# Power.net
KiCad netlist of a schematic drawn in Altium Designer
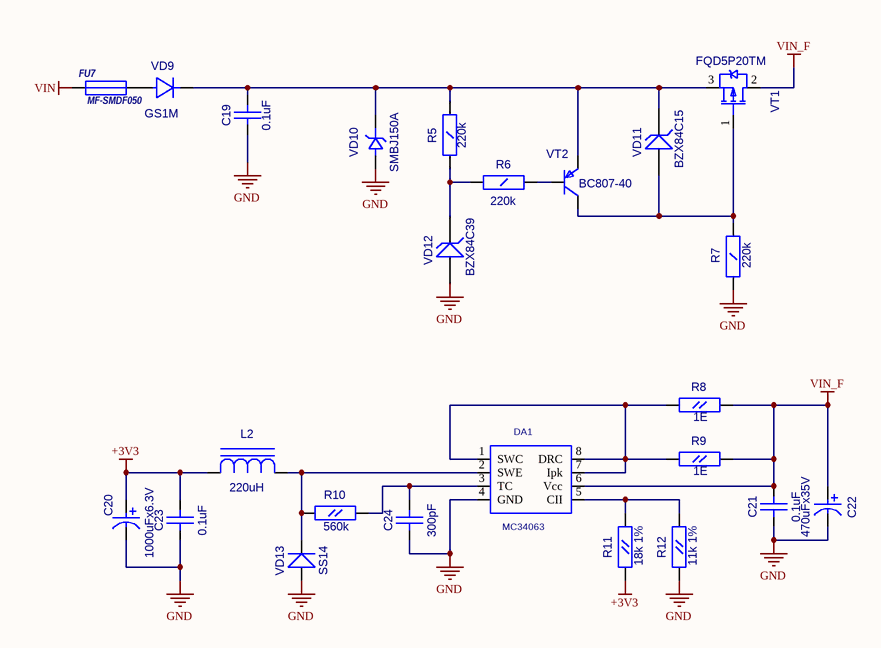
[diagram p0: Power.SchDoc]

(export (version "E")
  (design (tool "Eeschema 10.0.6"))
  (components
    (comp (ref "C19")
      (value "0.1uF")
      (footprint "CC1206")
      (description "CC1206")
      (libsource (lib "gprs_modem_2") (part "CC1206"))
    )
    (comp (ref "C20")
      (value "1000uFx6.3V")
      (footprint "CC8X3.5")
      (description "CAP0.35")
      (libsource (lib "gprs_modem_2") (part "CAP0.35"))
    )
    (comp (ref "C21")
      (value "0.1uF")
      (footprint "CC0603")
      (description "CC0603")
      (libsource (lib "gprs_modem_2") (part "CC0603"))
    )
    (comp (ref "C22")
      (value "470uFx35V")
      (footprint "CC16X10_CAP0.5(1)(Primary)")
      (description "CAP0.5(1)")
      (libsource (lib "gprs_modem_2") (part "CAP0.5(1)"))
    )
    (comp (ref "C23")
      (value "0.1uF")
      (footprint "CC0603")
      (description "CC0603")
      (libsource (lib "gprs_modem_2") (part "CC0603"))
    )
    (comp (ref "C24")
      (value "300pF")
      (footprint "CC0603")
      (description "CC0603")
      (libsource (lib "gprs_modem_2") (part "CC0603"))
    )
    (comp (ref "DA1") (value "MC34063") (footprint "SO-8") (libsource (lib "Schetchik") (part "MC34063")))
    (comp (ref "FU7")
      (value "MF-SMDF050")
      (footprint "MF-SMDF")
      (description "MF-SMDF")
      (libsource (lib "gprs_modem_2") (part "MF-SMDF"))
    )
    (comp (ref "L2")
      (value "220uH")
      (footprint "SDR0805")
      (description "SDR0805")
      (libsource (lib "gprs_modem_2") (part "SDR0805"))
    )
    (comp (ref "R5")
      (value "220k")
      (footprint "RC1206")
      (description "RC1206")
      (libsource (lib "gprs_modem_2") (part "RC1206"))
    )
    (comp (ref "R6")
      (value "220k")
      (footprint "RC1206")
      (description "RC1206")
      (libsource (lib "gprs_modem_2") (part "RC1206"))
    )
    (comp (ref "R7")
      (value "220k")
      (footprint "RC1206")
      (description "RC1206")
      (libsource (lib "gprs_modem_2") (part "RC1206"))
    )
    (comp (ref "R8")
      (value "1E")
      (footprint "RC0805")
      (description "RC0805")
      (libsource (lib "gprs_modem_2") (part "RC0805"))
    )
    (comp (ref "R9")
      (value "1E")
      (footprint "RC0805")
      (description "RC0805")
      (libsource (lib "gprs_modem_2") (part "RC0805"))
    )
    (comp (ref "R10")
      (value "560k")
      (footprint "RC0603")
      (description "RC0603")
      (libsource (lib "gprs_modem_2") (part "RC0603"))
    )
    (comp (ref "R11")
      (value "18k 1%")
      (footprint "RC0603")
      (description "RC0603")
      (libsource (lib "gprs_modem_2") (part "RC0603"))
    )
    (comp (ref "R12")
      (value "11k 1%")
      (footprint "RC0603")
      (description "RC0603")
      (libsource (lib "gprs_modem_2") (part "RC0603"))
    )
    (comp (ref "VD9") (value "GS1M") (footprint "SMA") (libsource (lib "gprs_modem") (part "GS1M")))
    (comp (ref "VD10")
      (value "SMBJ150A")
      (footprint "SMB")
      (description "SMBJ")
      (libsource (lib "gprs_modem_2") (part "SMBJ"))
    )
    (comp (ref "VD11")
      (value "BZX84C15")
      (footprint "SOT-23(123)")
      (description "Zener Voltage Regulator Diode")
      (libsource (lib "gprs_modem_2") (part "BZX84"))
    )
    (comp (ref "VD12")
      (value "BZX84C39")
      (footprint "SOT-23(123)")
      (description "Zener Voltage Regulator Diode")
      (libsource (lib "gprs_modem_2") (part "BZX84"))
    )
    (comp (ref "VD13")
      (value "SS14")
      (footprint "SMA")
      (description "Schottky Rectifier")
      (libsource (lib "gprs_modem_2") (part "SS14"))
    )
    (comp (ref "VT1")
      (value "FQD5P20TM")
      (footprint "D-PAK(TO-252AA)")
      (description "HEXFET Power MOSFET")
      (libsource (lib "gprs_modem_2") (part "IRFR9220"))
    )
    (comp (ref "VT2")
      (value "BC807-40")
      (footprint "SOT-23(123)")
      (description "BC857B")
      (libsource (lib "gprs_modem") (part "BC857B"))
    )
  )
  (nets
    (net (code "1") (name "+3V3") (class "Default")
      (node (ref "C20") (pin "1") (pintype "passive"))
      (node (ref "C23") (pin "2") (pinfunction "B_2") (pintype "passive"))
      (node (ref "L2") (pin "1") (pinfunction "C_1") (pintype "passive"))
      (node (ref "R11") (pin "1") (pinfunction "A_1") (pintype "passive"))
    )
    (net (code "2") (name "GND") (class "Default")
      (node (ref "C19") (pin "1") (pinfunction "A_1") (pintype "passive"))
      (node (ref "C20") (pin "2") (pintype "passive"))
      (node (ref "C21") (pin "1") (pinfunction "A_1") (pintype "passive"))
      (node (ref "C22") (pin "1") (pintype "passive"))
      (node (ref "C23") (pin "1") (pinfunction "A_1") (pintype "passive"))
      (node (ref "C24") (pin "1") (pinfunction "A_1") (pintype "passive"))
      (node (ref "DA1") (pin "4") (pinfunction "GND_4") (pintype "passive"))
      (node (ref "R12") (pin "1") (pinfunction "A_1") (pintype "passive"))
      (node (ref "R7") (pin "2") (pinfunction "B_2") (pintype "passive"))
      (node (ref "VD10") (pin "1") (pinfunction "A_1") (pintype "passive"))
      (node (ref "VD12") (pin "1") (pinfunction "A_1") (pintype "passive"))
      (node (ref "VD13") (pin "1") (pinfunction "A_1") (pintype "passive"))
    )
    (net (code "3") (name "Net-(C19-B)") (class "Default")
      (node (ref "C19") (pin "2") (pinfunction "B_2") (pintype "passive"))
      (node (ref "R5") (pin "2") (pinfunction "B_2") (pintype "passive"))
      (node (ref "VD10") (pin "2") (pinfunction "K_2") (pintype "passive"))
      (node (ref "VD11") (pin "3") (pinfunction "K_3") (pintype "passive"))
      (node (ref "VD9") (pin "2") (pinfunction "K_2") (pintype "passive"))
      (node (ref "VT1") (pin "3") (pinfunction "S_3") (pintype "passive"))
      (node (ref "VT2") (pin "2") (pinfunction "E_2") (pintype "passive"))
    )
    (net (code "4") (name "Net-(C24-B)") (class "Default")
      (node (ref "C24") (pin "2") (pinfunction "B_2") (pintype "passive"))
      (node (ref "DA1") (pin "3") (pinfunction "TC_3") (pintype "passive"))
      (node (ref "R10") (pin "2") (pinfunction "B_2") (pintype "passive"))
    )
    (net (code "5") (name "Net-(DA1-CII)") (class "Default")
      (node (ref "DA1") (pin "5") (pinfunction "CII_5") (pintype "passive"))
      (node (ref "R11") (pin "2") (pinfunction "B_2") (pintype "passive"))
      (node (ref "R12") (pin "2") (pinfunction "B_2") (pintype "passive"))
    )
    (net (code "6") (name "Net-(DA1-DRC)") (class "Default")
      (node (ref "DA1") (pin "1") (pinfunction "SWC_1") (pintype "passive"))
      (node (ref "DA1") (pin "7") (pinfunction "Ipk_7") (pintype "passive"))
      (node (ref "DA1") (pin "8") (pinfunction "DRC_8") (pintype "passive"))
      (node (ref "R8") (pin "1") (pinfunction "A_1") (pintype "passive"))
      (node (ref "R9") (pin "1") (pinfunction "A_1") (pintype "passive"))
    )
    (net (code "7") (name "Net-(DA1-SWE)") (class "Default")
      (node (ref "DA1") (pin "2") (pinfunction "SWE_2") (pintype "passive"))
      (node (ref "L2") (pin "2") (pinfunction "A_2") (pintype "passive"))
      (node (ref "R10") (pin "1") (pinfunction "A_1") (pintype "passive"))
      (node (ref "VD13") (pin "2") (pinfunction "K_2") (pintype "passive"))
    )
    (net (code "8") (name "Net-(R5-A)") (class "Default")
      (node (ref "R5") (pin "1") (pinfunction "A_1") (pintype "passive"))
      (node (ref "R6") (pin "1") (pinfunction "A_1") (pintype "passive"))
      (node (ref "VD12") (pin "3") (pinfunction "K_3") (pintype "passive"))
    )
    (net (code "9") (name "Net-(R6-B)") (class "Default")
      (node (ref "R6") (pin "2") (pinfunction "B_2") (pintype "passive"))
      (node (ref "VT2") (pin "1") (pinfunction "B_1") (pintype "passive"))
    )
    (net (code "10") (name "Net-(R7-A)") (class "Default")
      (node (ref "R7") (pin "1") (pinfunction "A_1") (pintype "passive"))
      (node (ref "VD11") (pin "1") (pinfunction "A_1") (pintype "passive"))
      (node (ref "VT1") (pin "1") (pinfunction "G_1") (pintype "passive"))
      (node (ref "VT2") (pin "3") (pinfunction "C_3") (pintype "passive"))
    )
    (net (code "11") (name "Net-(VD9-A)") (class "Default")
      (node (ref "FU7") (pin "2") (pintype "passive"))
      (node (ref "VD9") (pin "1") (pinfunction "A_1") (pintype "passive"))
    )
    (net (code "12") (name "VIN") (class "Default") (node (ref "FU7") (pin "1") (pintype "passive")))
    (net (code "13") (name "VIN_F") (class "Default")
      (node (ref "C21") (pin "2") (pinfunction "B_2") (pintype "passive"))
      (node (ref "C22") (pin "2") (pintype "passive"))
      (node (ref "DA1") (pin "6") (pinfunction "Vcc_6") (pintype "passive"))
      (node (ref "R8") (pin "2") (pinfunction "B_2") (pintype "passive"))
      (node (ref "R9") (pin "2") (pinfunction "B_2") (pintype "passive"))
      (node (ref "VT1") (pin "2") (pinfunction "D_2") (pintype "passive"))
    )
  )
)
